# CONNECTOR.net
KiCad netlist of a schematic drawn in Altium Designer
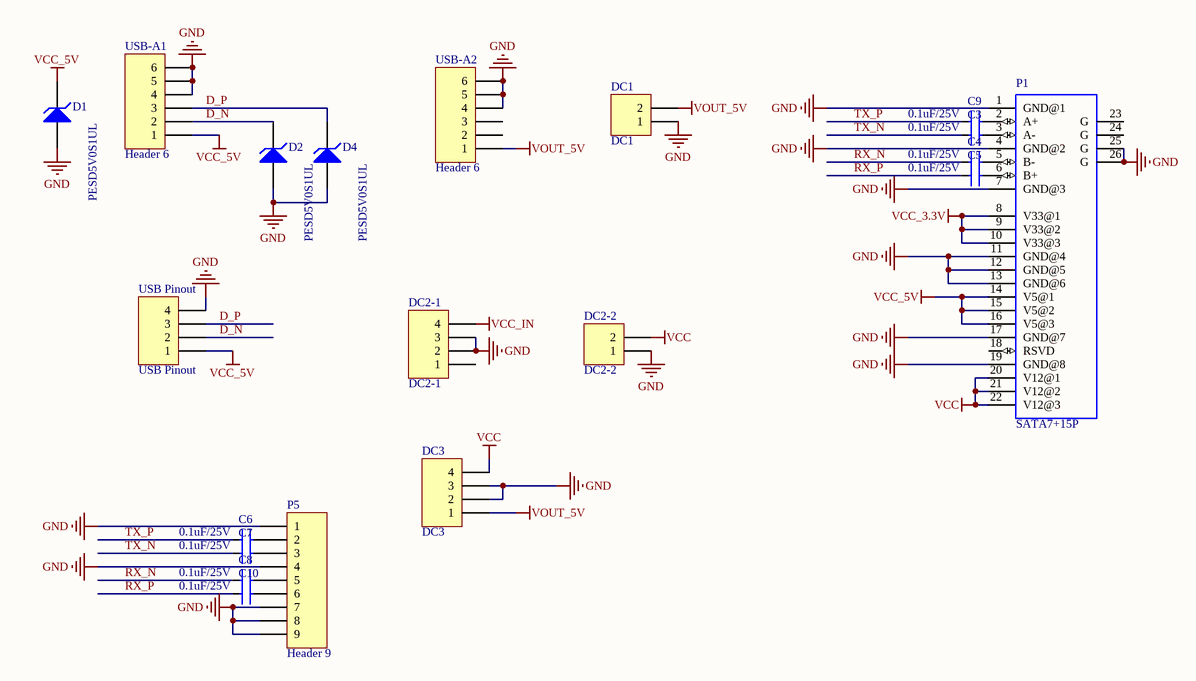
[diagram p0: CONNECTOR.SchDoc]

(export (version "E")
  (design (tool "Eeschema 10.0.6"))
  (components
    (comp (ref "C3")
      (value "0.1uF/25V")
      (footprint "0603C")
      (description "CCX85-103")
      (libsource (lib "无极性电容") (part "0.01UF"))
    )
    (comp (ref "C4")
      (value "0.1uF/25V")
      (footprint "0603C")
      (description "CCX85-103")
      (libsource (lib "无极性电容") (part "0.01UF"))
    )
    (comp (ref "C5")
      (value "0.1uF/25V")
      (footprint "0603C")
      (description "CCX85-103")
      (libsource (lib "无极性电容") (part "0.01UF"))
    )
    (comp (ref "C6")
      (value "0.1uF/25V")
      (footprint "0603C")
      (description "CCX85-103")
      (libsource (lib "无极性电容") (part "0.01UF"))
    )
    (comp (ref "C7")
      (value "0.1uF/25V")
      (footprint "0603C")
      (description "CCX85-103")
      (libsource (lib "无极性电容") (part "0.01UF"))
    )
    (comp (ref "C8")
      (value "0.1uF/25V")
      (footprint "0603C")
      (description "CCX85-103")
      (libsource (lib "无极性电容") (part "0.01UF"))
    )
    (comp (ref "C9")
      (value "0.1uF/25V")
      (footprint "0603C")
      (description "CCX85-103")
      (libsource (lib "无极性电容") (part "0.01UF"))
    )
    (comp (ref "C10")
      (value "0.1uF/25V")
      (footprint "0603C")
      (description "CCX85-103")
      (libsource (lib "无极性电容") (part "0.01UF"))
    )
    (comp (ref "D1")
      (value "PESD5V0S1UL")
      (footprint "0402R")
      (description "Zener Diode")
      (fields (field (name "PUBLISHER") "Altium Limited"))
      (libsource (lib "Miscellaneous Devices") (part "D Zener"))
    )
    (comp (ref "D2")
      (value "PESD5V0S1UL")
      (footprint "0402R")
      (description "Zener Diode")
      (fields (field (name "PUBLISHER") "Altium Limited"))
      (libsource (lib "Miscellaneous Devices") (part "D Zener"))
    )
    (comp (ref "D4")
      (value "PESD5V0S1UL")
      (footprint "0402R")
      (description "Zener Diode")
      (fields (field (name "PUBLISHER") "Altium Limited"))
      (libsource (lib "Miscellaneous Devices") (part "D Zener"))
    )
    (comp (ref "DC1")
      (value "DC1")
      (footprint "2X2MMZ")
      (description "Header, 2-Pin")
      (fields (field (name "PUBLISHER") "Altium Limited"))
      (libsource (lib "Miscellaneous Connectors") (part "Header 2"))
    )
    (comp (ref "DC2-1")
      (value "DC2-1")
      (footprint "DC005")
      (description "Header, 4-Pin")
      (fields (field (name "PUBLISHER") "Altium Limited"))
      (libsource (lib "Miscellaneous Connectors") (part "Header 4"))
    )
    (comp (ref "DC2-2")
      (value "DC2-2")
      (footprint "2X2MMZ")
      (description "Header, 2-Pin")
      (fields (field (name "PUBLISHER") "Altium Limited"))
      (libsource (lib "Miscellaneous Connectors") (part "Header 2"))
    )
    (comp (ref "DC3")
      (value "DC3")
      (footprint "2X4MMZ")
      (description "Header, 4-Pin")
      (fields (field (name "PUBLISHER") "Altium Limited"))
      (libsource (lib "Miscellaneous Connectors") (part "Header 4"))
    )
    (comp (ref "P1")
      (value "SATA7+15P")
      (footprint "SATA 7+15PML")
      (description "Conn SATA PL 15Power/7Signal POS 1.27mm Solder RA Thru-Hole 22 Terminal 1 Port")
      (fields (field (name "MF") "3M") (field (name "MP") "5622-4100-ML"))
      (libsource (lib "Schlib_20110825") (part "SATA7+15P"))
    )
    (comp (ref "P5")
      (value "Header 9")
      (footprint "SATA 7P")
      (description "Header, 9-Pin")
      (fields (field (name "PUBLISHER") "Altium Limited"))
      (libsource (lib "Miscellaneous Connectors") (part "Header 9"))
    )
    (comp (ref "USB Pinout")
      (value "USB Pinout")
      (footprint "sip-4l")
      (description "Header, 4-Pin")
      (fields (field (name "PUBLISHER") "Altium Limited"))
      (libsource (lib "Miscellaneous Connectors") (part "Header 4"))
    )
    (comp (ref "USB-A1")
      (value "Header 6")
      (footprint "USB-A-C")
      (description "Header, 6-Pin")
      (fields (field (name "PUBLISHER") "Altium Limited"))
      (libsource (lib "Miscellaneous Connectors") (part "Header 6"))
    )
    (comp (ref "USB-A2")
      (value "Header 6")
      (footprint "USB-A-C")
      (description "Header, 6-Pin")
      (fields (field (name "PUBLISHER") "Altium Limited"))
      (libsource (lib "Miscellaneous Connectors") (part "Header 6"))
    )
  )
  (nets
    (net (code "1") (name "/D_N") (class "Default")
      (node (ref "D2") (pin "2") (pinfunction "K_2") (pintype "passive"))
      (node (ref "USB Pinout") (pin "2") (pinfunction "2_2") (pintype "passive"))
      (node (ref "USB-A1") (pin "2") (pinfunction "2_2") (pintype "passive"))
    )
    (net (code "2") (name "/D_P") (class "Default")
      (node (ref "D4") (pin "2") (pinfunction "K_2") (pintype "passive"))
      (node (ref "USB Pinout") (pin "3") (pinfunction "3_3") (pintype "passive"))
      (node (ref "USB-A1") (pin "3") (pinfunction "3_3") (pintype "passive"))
    )
    (net (code "3") (name "/RX_N") (class "Default")
      (node (ref "C4") (pin "1") (pinfunction "1_1") (pintype "passive"))
      (node (ref "C8") (pin "1") (pinfunction "1_1") (pintype "passive"))
    )
    (net (code "4") (name "/RX_P") (class "Default")
      (node (ref "C10") (pin "1") (pinfunction "1_1") (pintype "passive"))
      (node (ref "C5") (pin "1") (pinfunction "1_1") (pintype "passive"))
    )
    (net (code "5") (name "/TX_N") (class "Default")
      (node (ref "C3") (pin "1") (pinfunction "1_1") (pintype "passive"))
      (node (ref "C7") (pin "1") (pinfunction "1_1") (pintype "passive"))
    )
    (net (code "6") (name "/TX_P") (class "Default")
      (node (ref "C6") (pin "1") (pinfunction "1_1") (pintype "passive"))
      (node (ref "C9") (pin "1") (pinfunction "1_1") (pintype "passive"))
    )
    (net (code "7") (name "GND") (class "Default")
      (node (ref "D1") (pin "1") (pinfunction "A_1") (pintype "passive"))
      (node (ref "D2") (pin "1") (pinfunction "A_1") (pintype "passive"))
      (node (ref "D4") (pin "1") (pinfunction "A_1") (pintype "passive"))
      (node (ref "DC1") (pin "1") (pinfunction "1_1") (pintype "passive"))
      (node (ref "DC2-1") (pin "2") (pinfunction "2_2") (pintype "passive"))
      (node (ref "DC2-1") (pin "3") (pinfunction "3_3") (pintype "passive"))
      (node (ref "DC2-2") (pin "1") (pinfunction "1_1") (pintype "passive"))
      (node (ref "DC3") (pin "2") (pinfunction "2_2") (pintype "passive"))
      (node (ref "DC3") (pin "3") (pinfunction "3_3") (pintype "passive"))
      (node (ref "P1") (pin "1") (pinfunction "GND@1_1") (pintype "power_in"))
      (node (ref "P1") (pin "11") (pinfunction "GND@4_11") (pintype "power_in"))
      (node (ref "P1") (pin "12") (pinfunction "GND@5_12") (pintype "power_in"))
      (node (ref "P1") (pin "13") (pinfunction "GND@6_13") (pintype "power_in"))
      (node (ref "P1") (pin "17") (pinfunction "GND@7_17") (pintype "power_in"))
      (node (ref "P1") (pin "19") (pinfunction "GND@8_19") (pintype "power_in"))
      (node (ref "P1") (pin "25") (pinfunction "G_25") (pintype "power_in"))
      (node (ref "P1") (pin "26") (pinfunction "G_26") (pintype "power_in"))
      (node (ref "P1") (pin "4") (pinfunction "GND@2_4") (pintype "power_in"))
      (node (ref "P1") (pin "7") (pinfunction "GND@3_7") (pintype "power_in"))
      (node (ref "P5") (pin "1") (pinfunction "1_1") (pintype "passive"))
      (node (ref "P5") (pin "4") (pinfunction "4_4") (pintype "passive"))
      (node (ref "P5") (pin "7") (pinfunction "7_7") (pintype "passive"))
      (node (ref "P5") (pin "8") (pinfunction "8_8") (pintype "passive"))
      (node (ref "P5") (pin "9") (pinfunction "9_9") (pintype "passive"))
      (node (ref "USB Pinout") (pin "4") (pinfunction "4_4") (pintype "passive"))
      (node (ref "USB-A1") (pin "4") (pinfunction "4_4") (pintype "passive"))
      (node (ref "USB-A1") (pin "5") (pinfunction "5_5") (pintype "passive"))
      (node (ref "USB-A1") (pin "6") (pinfunction "6_6") (pintype "passive"))
      (node (ref "USB-A2") (pin "4") (pinfunction "4_4") (pintype "passive"))
      (node (ref "USB-A2") (pin "5") (pinfunction "5_5") (pintype "passive"))
      (node (ref "USB-A2") (pin "6") (pinfunction "6_6") (pintype "passive"))
    )
    (net (code "8") (name "Net-(C6-Pad2)") (class "Default")
      (node (ref "C6") (pin "2") (pinfunction "2_2") (pintype "passive"))
      (node (ref "P5") (pin "2") (pinfunction "2_2") (pintype "passive"))
    )
    (net (code "9") (name "Net-(C7-Pad2)") (class "Default")
      (node (ref "C7") (pin "2") (pinfunction "2_2") (pintype "passive"))
      (node (ref "P5") (pin "3") (pinfunction "3_3") (pintype "passive"))
    )
    (net (code "10") (name "Net-(C8-Pad2)") (class "Default")
      (node (ref "C8") (pin "2") (pinfunction "2_2") (pintype "passive"))
      (node (ref "P5") (pin "5") (pinfunction "5_5") (pintype "passive"))
    )
    (net (code "11") (name "Net-(C10-Pad2)") (class "Default")
      (node (ref "C10") (pin "2") (pinfunction "2_2") (pintype "passive"))
      (node (ref "P5") (pin "6") (pinfunction "6_6") (pintype "passive"))
    )
    (net (code "12") (name "Net-(P1-A+)") (class "Default")
      (node (ref "C9") (pin "2") (pinfunction "2_2") (pintype "passive"))
      (node (ref "P1") (pin "2") (pinfunction "A+_2") (pintype "bidirectional"))
    )
    (net (code "13") (name "Net-(P1-A-)") (class "Default")
      (node (ref "C3") (pin "2") (pinfunction "2_2") (pintype "passive"))
      (node (ref "P1") (pin "3") (pinfunction "A-_3") (pintype "bidirectional"))
    )
    (net (code "14") (name "Net-(P1-B+)") (class "Default")
      (node (ref "C5") (pin "2") (pinfunction "2_2") (pintype "passive"))
      (node (ref "P1") (pin "6") (pinfunction "B+_6") (pintype "bidirectional"))
    )
    (net (code "15") (name "Net-(P1-B-)") (class "Default")
      (node (ref "C4") (pin "2") (pinfunction "2_2") (pintype "passive"))
      (node (ref "P1") (pin "5") (pinfunction "B-_5") (pintype "bidirectional"))
    )
    (net (code "16") (name "VCC") (class "Default")
      (node (ref "DC2-2") (pin "2") (pinfunction "2_2") (pintype "passive"))
      (node (ref "DC3") (pin "4") (pinfunction "4_4") (pintype "passive"))
      (node (ref "P1") (pin "20") (pinfunction "V12@1_20") (pintype "power_in"))
      (node (ref "P1") (pin "21") (pinfunction "V12@2_21") (pintype "power_in"))
      (node (ref "P1") (pin "22") (pinfunction "V12@3_22") (pintype "power_in"))
    )
    (net (code "17") (name "VCC_3.3V") (class "Default")
      (node (ref "P1") (pin "10") (pinfunction "V33@3_10") (pintype "power_in"))
      (node (ref "P1") (pin "8") (pinfunction "V33@1_8") (pintype "power_in"))
      (node (ref "P1") (pin "9") (pinfunction "V33@2_9") (pintype "power_in"))
    )
    (net (code "18") (name "VCC_5V") (class "Default")
      (node (ref "D1") (pin "2") (pinfunction "K_2") (pintype "passive"))
      (node (ref "P1") (pin "14") (pinfunction "V5@1_14") (pintype "power_in"))
      (node (ref "P1") (pin "15") (pinfunction "V5@2_15") (pintype "power_in"))
      (node (ref "P1") (pin "16") (pinfunction "V5@3_16") (pintype "power_in"))
      (node (ref "USB Pinout") (pin "1") (pinfunction "1_1") (pintype "passive"))
      (node (ref "USB-A1") (pin "1") (pinfunction "1_1") (pintype "passive"))
    )
    (net (code "19") (name "VCC_IN") (class "Default")
      (node (ref "DC2-1") (pin "4") (pinfunction "4_4") (pintype "passive"))
    )
    (net (code "20") (name "VOUT_5V") (class "Default")
      (node (ref "DC1") (pin "2") (pinfunction "2_2") (pintype "passive"))
      (node (ref "DC3") (pin "1") (pinfunction "1_1") (pintype "passive"))
      (node (ref "USB-A2") (pin "1") (pinfunction "1_1") (pintype "passive"))
    )
    (net (code "21") (name "unconnected-(DC2-1-Pad1)") (class "Default")
      (node (ref "DC2-1") (pin "1") (pinfunction "1_1") (pintype "passive"))
    )
    (net (code "22") (name "unconnected-(P1-G-Pad23)") (class "Default")
      (node (ref "P1") (pin "23") (pinfunction "G_23") (pintype "power_in"))
    )
    (net (code "23") (name "unconnected-(P1-G-Pad24)") (class "Default")
      (node (ref "P1") (pin "24") (pinfunction "G_24") (pintype "power_in"))
    )
    (net (code "24") (name "unconnected-(P1-RSVD-Pad18)") (class "Default")
      (node (ref "P1") (pin "18") (pinfunction "RSVD_18") (pintype "bidirectional"))
    )
    (net (code "25") (name "unconnected-(USB-A2-Pad2)") (class "Default")
      (node (ref "USB-A2") (pin "2") (pinfunction "2_2") (pintype "passive"))
    )
    (net (code "26") (name "unconnected-(USB-A2-Pad3)") (class "Default")
      (node (ref "USB-A2") (pin "3") (pinfunction "3_3") (pintype "passive"))
    )
  )
)
